# 5v_dual_power_supply.net
KiCad netlist of a schematic drawn in EAGLE
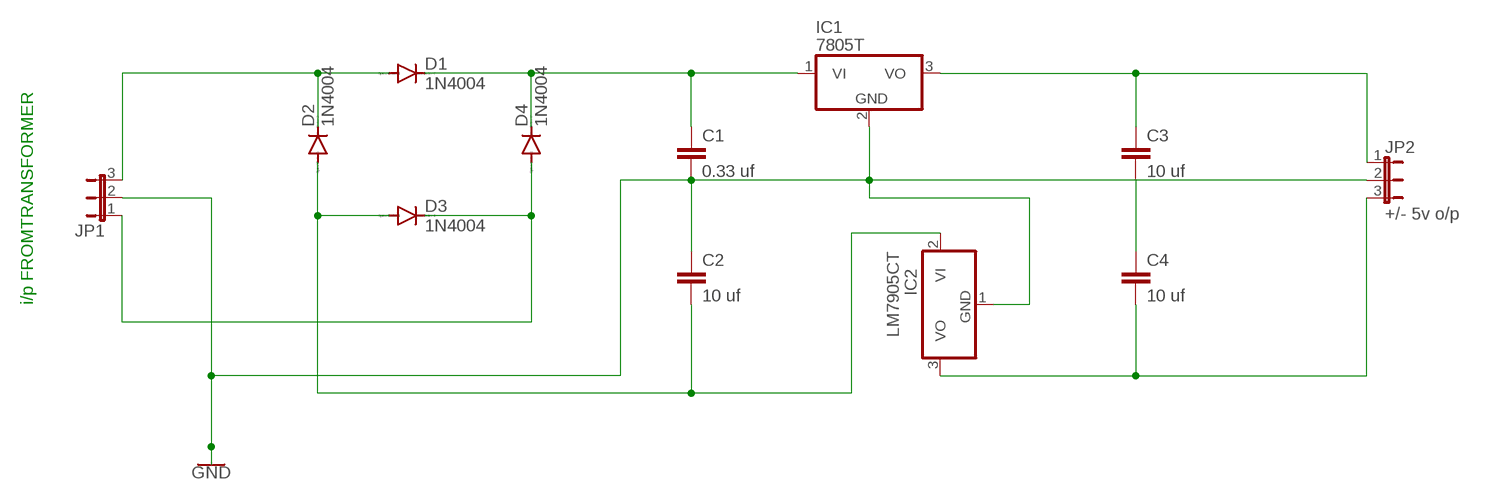
[diagram p0: schematic, sheet 1]

(export (version "E")
  (design (tool "Eeschema 10.0.6"))
  (components
    (comp (ref "C1")
      (value "0.33 uf")
      (footprint "eagle-import:C2.5-3")
      (libsource (lib "eagle-import") (part "C2,5-3"))
    )
    (comp (ref "C2")
      (value "10 uf")
      (footprint "eagle-import:C2.5-3")
      (libsource (lib "eagle-import") (part "C2,5-3"))
    )
    (comp (ref "C3")
      (value "10 uf")
      (footprint "eagle-import:C2.5-3")
      (libsource (lib "eagle-import") (part "C2,5-3"))
    )
    (comp (ref "C4")
      (value "10 uf")
      (footprint "eagle-import:C2.5-3")
      (libsource (lib "eagle-import") (part "C2,5-3"))
    )
    (comp (ref "D1")
      (value "1N4004")
      (footprint "eagle-import:DO41-10")
      (libsource (lib "eagle-import") (part "1N4004"))
    )
    (comp (ref "D2")
      (value "1N4004")
      (footprint "eagle-import:DO41-10")
      (libsource (lib "eagle-import") (part "1N4004"))
    )
    (comp (ref "D3")
      (value "1N4004")
      (footprint "eagle-import:DO41-10")
      (libsource (lib "eagle-import") (part "1N4004"))
    )
    (comp (ref "D4")
      (value "1N4004")
      (footprint "eagle-import:DO41-10")
      (libsource (lib "eagle-import") (part "1N4004"))
    )
    (comp (ref "IC1")
      (value "7805T")
      (footprint "eagle-import:TO220H")
      (libsource (lib "eagle-import") (part "78T05"))
    )
    (comp (ref "IC2")
      (value "LM7905CT")
      (footprint "eagle-import:TO220H")
      (libsource (lib "eagle-import") (part "79T05"))
    )
    (comp (ref "JP1")
      (value "JP2E")
      (footprint "eagle-import:JP2")
      (libsource (lib "eagle-import") (part "JP2E"))
    )
    (comp (ref "JP2")
      (value "+/- 5v o/p")
      (footprint "eagle-import:JP2")
      (libsource (lib "eagle-import") (part "JP2E"))
    )
  )
  (nets
    (net (code "1") (name "GND") (class "Default")
      (node (ref "C1") (pin "2") (pinfunction "2_2") (pintype "passive"))
      (node (ref "C2") (pin "1") (pinfunction "1_1") (pintype "passive"))
      (node (ref "IC1") (pin "2") (pinfunction "GND_2") (pintype "passive"))
      (node (ref "IC2") (pin "1") (pinfunction "GND_1") (pintype "passive"))
      (node (ref "JP1") (pin "2") (pinfunction "2_2") (pintype "passive"))
      (node (ref "JP2") (pin "2") (pinfunction "2_2") (pintype "passive"))
    )
    (net (code "2") (name "Net-(C3-Pad2)") (class "Default")
      (node (ref "C3") (pin "2") (pinfunction "2_2") (pintype "passive"))
      (node (ref "C4") (pin "1") (pinfunction "1_1") (pintype "passive"))
    )
    (net (code "3") (name "Net-(D1-PadA)") (class "Default")
      (node (ref "D1") (pin "A") (pinfunction "A_A") (pintype "passive"))
      (node (ref "D2") (pin "C") (pinfunction "C_C") (pintype "passive"))
      (node (ref "JP1") (pin "3") (pinfunction "3_3") (pintype "passive"))
    )
    (net (code "4") (name "Net-(D3-PadC)") (class "Default")
      (node (ref "D3") (pin "C") (pinfunction "C_C") (pintype "passive"))
      (node (ref "D4") (pin "A") (pinfunction "A_A") (pintype "passive"))
      (node (ref "JP1") (pin "1") (pinfunction "1_1") (pintype "passive"))
    )
    (net (code "5") (name "Net-(IC1-VI)") (class "Default")
      (node (ref "C1") (pin "1") (pinfunction "1_1") (pintype "passive"))
      (node (ref "D1") (pin "C") (pinfunction "C_C") (pintype "passive"))
      (node (ref "D4") (pin "C") (pinfunction "C_C") (pintype "passive"))
      (node (ref "IC1") (pin "1") (pinfunction "VI_1") (pintype "input"))
    )
    (net (code "6") (name "Net-(IC1-VO)") (class "Default")
      (node (ref "C3") (pin "1") (pinfunction "1_1") (pintype "passive"))
      (node (ref "IC1") (pin "3") (pinfunction "VO_3") (pintype "passive"))
      (node (ref "JP2") (pin "1") (pinfunction "1_1") (pintype "passive"))
    )
    (net (code "7") (name "Net-(IC2-VI)") (class "Default")
      (node (ref "C2") (pin "2") (pinfunction "2_2") (pintype "passive"))
      (node (ref "D2") (pin "A") (pinfunction "A_A") (pintype "passive"))
      (node (ref "D3") (pin "A") (pinfunction "A_A") (pintype "passive"))
      (node (ref "IC2") (pin "2") (pinfunction "VI_2") (pintype "input"))
    )
    (net (code "8") (name "Net-(IC2-VO)") (class "Default")
      (node (ref "C4") (pin "2") (pinfunction "2_2") (pintype "passive"))
      (node (ref "IC2") (pin "3") (pinfunction "VO_3") (pintype "passive"))
      (node (ref "JP2") (pin "3") (pinfunction "3_3") (pintype "passive"))
    )
  )
)
